# totaal.net
KiCad netlist of a schematic drawn in Altium Designer
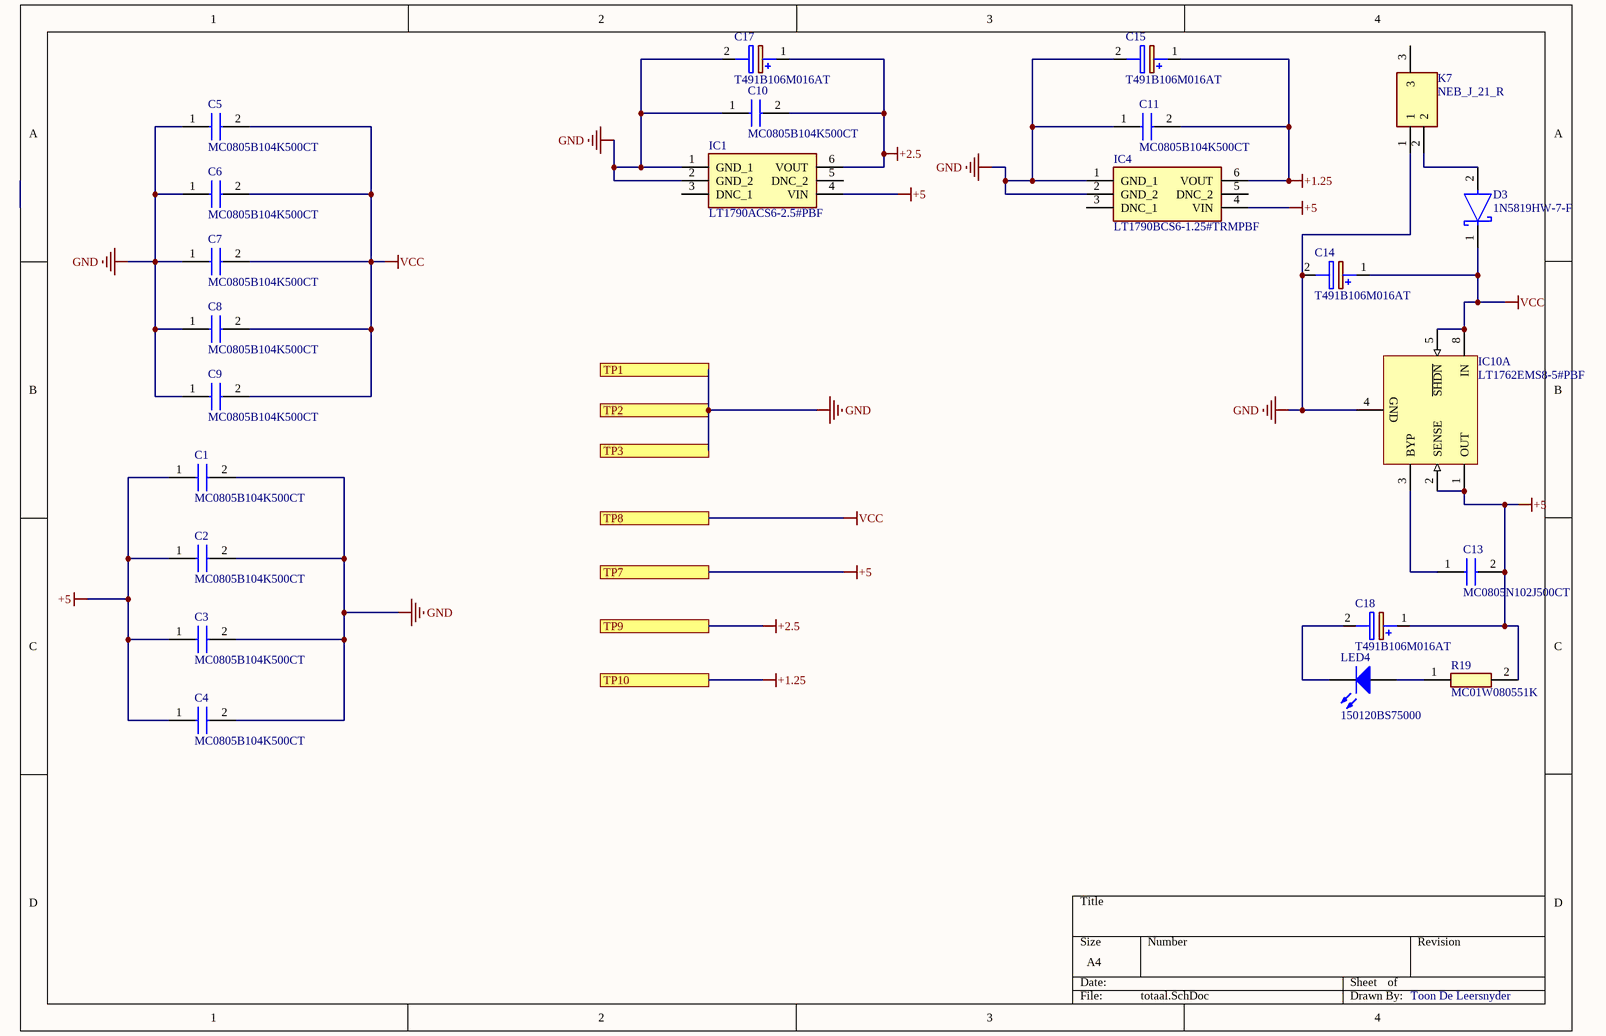
[diagram p0: totaal.SchDoc]

(export (version "E")
  (design (tool "Eeschema 10.0.6"))
  (components
    (comp (ref "C1")
      (value "MC0805B104K500CT")
      (footprint "SamacSys:CAPC2012X90N")
      (description "Capacitor")
      (libsource (lib "SamacSys") (part "MC0805B104K500CT"))
    )
    (comp (ref "C2")
      (value "MC0805B104K500CT")
      (footprint "SamacSys:CAPC2012X90N")
      (description "Capacitor")
      (libsource (lib "SamacSys") (part "MC0805B104K500CT"))
    )
    (comp (ref "C3")
      (value "MC0805B104K500CT")
      (footprint "SamacSys:CAPC2012X90N")
      (description "Capacitor")
      (libsource (lib "SamacSys") (part "MC0805B104K500CT"))
    )
    (comp (ref "C4")
      (value "MC0805B104K500CT")
      (footprint "SamacSys:CAPC2012X90N")
      (description "Capacitor")
      (libsource (lib "SamacSys") (part "MC0805B104K500CT"))
    )
    (comp (ref "C5")
      (value "MC0805B104K500CT")
      (footprint "SamacSys:CAPC2012X90N")
      (description "Capacitor")
      (libsource (lib "SamacSys") (part "MC0805B104K500CT"))
    )
    (comp (ref "C6")
      (value "MC0805B104K500CT")
      (footprint "SamacSys:CAPC2012X90N")
      (description "Capacitor")
      (libsource (lib "SamacSys") (part "MC0805B104K500CT"))
    )
    (comp (ref "C7")
      (value "MC0805B104K500CT")
      (footprint "SamacSys:CAPC2012X90N")
      (description "Capacitor")
      (libsource (lib "SamacSys") (part "MC0805B104K500CT"))
    )
    (comp (ref "C8")
      (value "MC0805B104K500CT")
      (footprint "SamacSys:CAPC2012X90N")
      (description "Capacitor")
      (libsource (lib "SamacSys") (part "MC0805B104K500CT"))
    )
    (comp (ref "C9")
      (value "MC0805B104K500CT")
      (footprint "SamacSys:CAPC2012X90N")
      (description "Capacitor")
      (libsource (lib "SamacSys") (part "MC0805B104K500CT"))
    )
    (comp (ref "C10")
      (value "MC0805B104K500CT")
      (footprint "SamacSys:CAPC2012X90N")
      (description "Capacitor")
      (libsource (lib "SamacSys") (part "MC0805B104K500CT"))
    )
    (comp (ref "C11")
      (value "MC0805B104K500CT")
      (footprint "SamacSys:CAPC2012X90N")
      (description "Capacitor")
      (libsource (lib "SamacSys") (part "MC0805B104K500CT"))
    )
    (comp (ref "C13")
      (value "MC0805N102J500CT")
      (footprint "SamacSys:CAPC2012X90N")
      (description "Capacitor")
      (libsource (lib "SamacSys") (part "MC0805N102J500CT"))
    )
    (comp (ref "C14")
      (value "T491B106M016AT")
      (footprint "SamacSys:CAPPM3528X210N")
      (description "Capacitor Polarised")
      (fields (field (name "MOUSER PART NUMBER") "80-T491B106M016"))
      (libsource (lib "SamacSys") (part "T491B106M016AT"))
    )
    (comp (ref "C15")
      (value "T491B106M016AT")
      (footprint "SamacSys:CAPPM3528X210N")
      (description "Capacitor Polarised")
      (fields (field (name "MOUSER PART NUMBER") "80-T491B106M016"))
      (libsource (lib "SamacSys") (part "T491B106M016AT"))
    )
    (comp (ref "C17")
      (value "T491B106M016AT")
      (footprint "SamacSys:CAPPM3528X210N")
      (description "Capacitor Polarised")
      (fields (field (name "MOUSER PART NUMBER") "80-T491B106M016"))
      (libsource (lib "SamacSys") (part "T491B106M016AT"))
    )
    (comp (ref "C18")
      (value "T491B106M016AT")
      (footprint "SamacSys:CAPPM3528X210N")
      (description "Capacitor Polarised")
      (fields (field (name "MOUSER PART NUMBER") "80-T491B106M016"))
      (libsource (lib "SamacSys") (part "T491B106M016AT"))
    )
    (comp (ref "D3")
      (value "1N5819HW-7-F")
      (footprint "FP-SOD123-IPC_B")
      (description "DIODE SCHOTTKY 40V 1A SOD123")
      (libsource (lib "Altium Content Vault") (part "1d6ec82d83fb6aee721767c19dac4b9"))
    )
    (comp (ref "IC1")
      (value "LT1790ACS6-2.5#PBF")
      (footprint "SamacSys:SOT95P280X100-6N")
      (description "Integrated Circuit")
      (fields (field (name "MOUSER PART NUMBER") "584-1790ACS6-2.5PBF"))
      (libsource (lib "SamacSys") (part "LT1790ACS6-2.5#PBF"))
    )
    (comp (ref "IC4")
      (value "LT1790BCS6-1.25#TRMPBF")
      (footprint "SamacSys:LT1790BCS6125TRMPBF")
      (description "Integrated Circuit")
      (fields (field (name "MOUSER PART NUMBER") "584-1790BCS61.25TMPF"))
      (libsource (lib "SamacSys") (part "LT1790BCS6-1.25#TRMPBF"))
    )
    (comp (ref "IC10")
      (value "LT1762EMS8-5#PBF")
      (footprint "LT-MS8_N")
      (fields (field (name "MANUFACTURER") "Linear Technology"))
      (libsource (lib "Altium Content Vault") (part "LT-LT1X62-MS8-8"))
    )
    (comp (ref "K7")
      (value "NEB_J_21_R")
      (footprint "SamacSys:NEBJ21R")
      (description "Connector")
      (fields (field (name "MANUFACTURER_PART_NUMBER") "NEB/J 21 R"))
      (libsource (lib "SamacSys") (part "NEB_J_21_R"))
    )
    (comp (ref "LED4")
      (value "150120BS75000")
      (footprint "1206_A")
      (description "SMD mono-color Chip LED, WL-SMCW, Blue")
      (fields (field (name "MANUFACTURER") "Wuerth Elektronik"))
      (libsource (lib "Altium Content Vault") (part "WE-LED_K1A2-2"))
    )
    (comp (ref "R19")
      (value "MC01W080551K")
      (footprint "SamacSys:RESC2014X65N")
      (description "Resistor")
      (libsource (lib "SamacSys") (part "MC01W080551K"))
    )
  )
  (nets
    (net (code "1") (name "+1.25") (class "Default")
      (node (ref "C11") (pin "2") (pinfunction "2_2") (pintype "passive"))
      (node (ref "C15") (pin "1") (pinfunction "+_1") (pintype "passive"))
      (node (ref "IC4") (pin "6") (pinfunction "VOUT_6") (pintype "passive"))
    )
    (net (code "2") (name "+2.5") (class "Default")
      (node (ref "C10") (pin "2") (pinfunction "2_2") (pintype "passive"))
      (node (ref "C17") (pin "1") (pinfunction "+_1") (pintype "passive"))
      (node (ref "IC1") (pin "6") (pinfunction "VOUT_6") (pintype "passive"))
    )
    (net (code "3") (name "+5") (class "Default")
      (node (ref "C1") (pin "1") (pinfunction "1_1") (pintype "passive"))
      (node (ref "C13") (pin "2") (pinfunction "2_2") (pintype "passive"))
      (node (ref "C18") (pin "1") (pinfunction "+_1") (pintype "passive"))
      (node (ref "C2") (pin "1") (pinfunction "1_1") (pintype "passive"))
      (node (ref "C3") (pin "1") (pinfunction "1_1") (pintype "passive"))
      (node (ref "C4") (pin "1") (pinfunction "1_1") (pintype "passive"))
      (node (ref "IC1") (pin "4") (pinfunction "VIN_4") (pintype "passive"))
      (node (ref "IC10") (pin "1") (pinfunction "OUT_1") (pintype "power_in"))
      (node (ref "IC10") (pin "2") (pinfunction "SENSE_2") (pintype "input"))
      (node (ref "IC4") (pin "4") (pinfunction "VIN_4") (pintype "passive"))
      (node (ref "R19") (pin "2") (pinfunction "2_2") (pintype "passive"))
    )
    (net (code "4") (name "GND") (class "Default")
      (node (ref "C1") (pin "2") (pinfunction "2_2") (pintype "passive"))
      (node (ref "C10") (pin "1") (pinfunction "1_1") (pintype "passive"))
      (node (ref "C11") (pin "1") (pinfunction "1_1") (pintype "passive"))
      (node (ref "C14") (pin "2") (pinfunction "-_2") (pintype "passive"))
      (node (ref "C15") (pin "2") (pinfunction "-_2") (pintype "passive"))
      (node (ref "C17") (pin "2") (pinfunction "-_2") (pintype "passive"))
      (node (ref "C2") (pin "2") (pinfunction "2_2") (pintype "passive"))
      (node (ref "C3") (pin "2") (pinfunction "2_2") (pintype "passive"))
      (node (ref "C4") (pin "2") (pinfunction "2_2") (pintype "passive"))
      (node (ref "C5") (pin "1") (pinfunction "1_1") (pintype "passive"))
      (node (ref "C6") (pin "1") (pinfunction "1_1") (pintype "passive"))
      (node (ref "C7") (pin "1") (pinfunction "1_1") (pintype "passive"))
      (node (ref "C8") (pin "1") (pinfunction "1_1") (pintype "passive"))
      (node (ref "C9") (pin "1") (pinfunction "1_1") (pintype "passive"))
      (node (ref "IC1") (pin "1") (pinfunction "GND_1_1") (pintype "passive"))
      (node (ref "IC1") (pin "2") (pinfunction "GND_2_2") (pintype "passive"))
      (node (ref "IC10") (pin "4") (pinfunction "GND_4") (pintype "power_in"))
      (node (ref "IC4") (pin "1") (pinfunction "GND_1_1") (pintype "passive"))
      (node (ref "IC4") (pin "2") (pinfunction "GND_2_2") (pintype "passive"))
      (node (ref "K7") (pin "1") (pinfunction "1_1") (pintype "passive"))
    )
    (net (code "5") (name "Net-(C18--)") (class "Default")
      (node (ref "C18") (pin "2") (pinfunction "-_2") (pintype "passive"))
      (node (ref "LED4") (pin "1") (pinfunction "K_1") (pintype "passive"))
    )
    (net (code "6") (name "Net-(D3-A)") (class "Default")
      (node (ref "D3") (pin "2") (pinfunction "A_2") (pintype "passive"))
      (node (ref "K7") (pin "2") (pinfunction "2_2") (pintype "passive"))
    )
    (net (code "7") (name "Net-(IC10A-BYP)") (class "Default")
      (node (ref "C13") (pin "1") (pinfunction "1_1") (pintype "passive"))
      (node (ref "IC10") (pin "3") (pinfunction "BYP_3") (pintype "passive"))
    )
    (net (code "8") (name "Net-(LED4-A)") (class "Default")
      (node (ref "LED4") (pin "2") (pinfunction "A_2") (pintype "passive"))
      (node (ref "R19") (pin "1") (pinfunction "1_1") (pintype "passive"))
    )
    (net (code "9") (name "VCC") (class "Default")
      (node (ref "C14") (pin "1") (pinfunction "+_1") (pintype "passive"))
      (node (ref "C5") (pin "2") (pinfunction "2_2") (pintype "passive"))
      (node (ref "C6") (pin "2") (pinfunction "2_2") (pintype "passive"))
      (node (ref "C7") (pin "2") (pinfunction "2_2") (pintype "passive"))
      (node (ref "C8") (pin "2") (pinfunction "2_2") (pintype "passive"))
      (node (ref "C9") (pin "2") (pinfunction "2_2") (pintype "passive"))
      (node (ref "D3") (pin "1") (pinfunction "C_1") (pintype "passive"))
      (node (ref "IC10") (pin "5") (pinfunction "~{SHDN}_5") (pintype "input"))
      (node (ref "IC10") (pin "8") (pinfunction "IN_8") (pintype "power_in"))
    )
    (net (code "10") (name "unconnected-(IC1-DNC_1-Pad3)") (class "Default")
      (node (ref "IC1") (pin "3") (pinfunction "DNC_1_3") (pintype "passive"))
    )
    (net (code "11") (name "unconnected-(IC1-DNC_2-Pad5)") (class "Default")
      (node (ref "IC1") (pin "5") (pinfunction "DNC_2_5") (pintype "passive"))
    )
    (net (code "12") (name "unconnected-(IC4-DNC_1-Pad3)") (class "Default")
      (node (ref "IC4") (pin "3") (pinfunction "DNC_1_3") (pintype "passive"))
    )
    (net (code "13") (name "unconnected-(IC4-DNC_2-Pad5)") (class "Default")
      (node (ref "IC4") (pin "5") (pinfunction "DNC_2_5") (pintype "passive"))
    )
    (net (code "14") (name "unconnected-(K7-Pad3)") (class "Default")
      (node (ref "K7") (pin "3") (pinfunction "3_3") (pintype "passive"))
    )
  )
)
